# tmc4671_InterfaceConnectors.net
KiCad netlist of a schematic drawn in Altium Designer
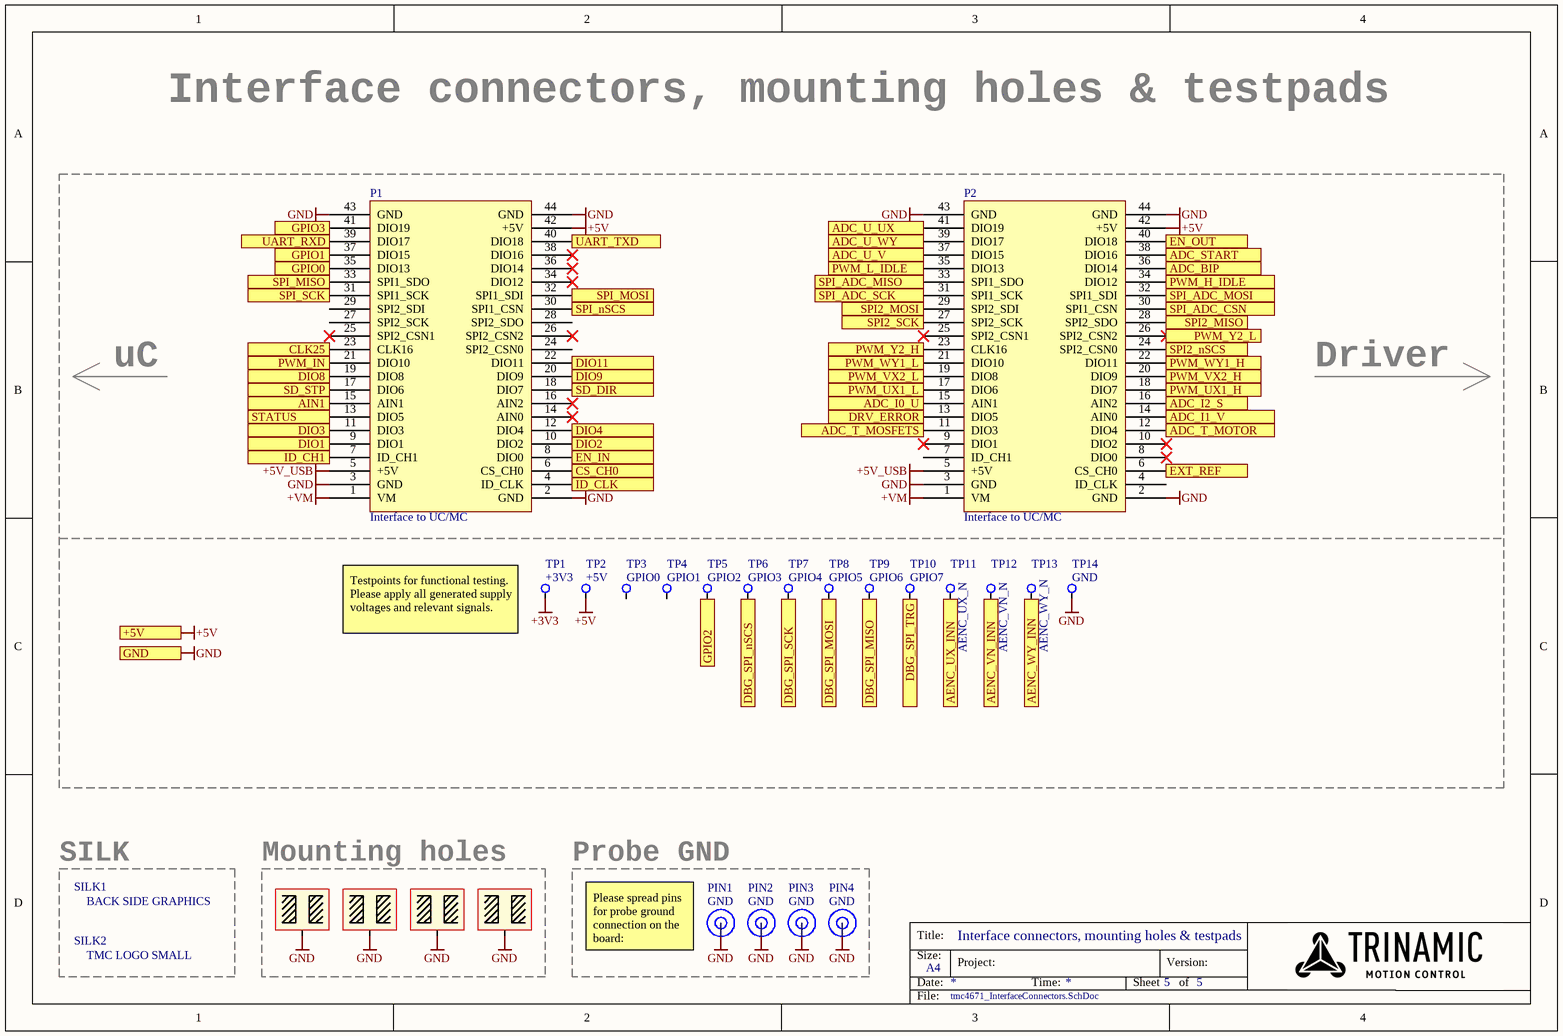
[diagram p0: tmc4671_InterfaceConnectors.SchDoc]

(export (version "E")
  (design (tool "Eeschema 10.0.6"))
  (components
    (comp (ref "MNT1")
      (value "MOUNTING_HOLE")
      (footprint "MNT_HOLE_6.35-3.2")
      (libsource (lib "TMC-EVAL_TMPL_V1_0") (part "MOUNTING_HOLE"))
    )
    (comp (ref "MNT2")
      (value "MOUNTING_HOLE")
      (footprint "MNT_HOLE_6.35-3.2")
      (libsource (lib "TMC-EVAL_TMPL_V1_0") (part "MOUNTING_HOLE"))
    )
    (comp (ref "MNT3")
      (value "MOUNTING_HOLE")
      (footprint "MNT_HOLE_6.35-3.2")
      (libsource (lib "TMC-EVAL_TMPL_V1_0") (part "MOUNTING_HOLE"))
    )
    (comp (ref "MNT4")
      (value "MOUNTING_HOLE")
      (footprint "MNT_HOLE_6.35-3.2")
      (libsource (lib "TMC-EVAL_TMPL_V1_0") (part "MOUNTING_HOLE"))
    )
    (comp (ref "P1")
      (value "Interface to UC/MC")
      (footprint "Interface_Connector")
      (description "Board-To-Board Connector, 2.54 mm, 44 Contacts, Receptacle, HLE Series, Surface Mount, 2 Rows")
      (fields (field (name "MF") "SAMTEC") (field (name "MPN") "HLE-122-02-L-DV"))
      (libsource (lib "TMC4671-EVAL_V1_0") (part "Interface Connector, 44 Pins"))
    )
    (comp (ref "P2")
      (value "Interface to UC/MC")
      (footprint "Interface_Connector")
      (description "Board-To-Board Connector, 2.54 mm, 44 Contacts, Receptacle, HLE Series, Surface Mount, 2 Rows")
      (fields (field (name "MF") "SAMTEC") (field (name "MPN") "HLE-122-02-L-DV"))
      (libsource (lib "TMC4671-EVAL_V1_0") (part "Interface Connector, 44 Pins"))
    )
    (comp (ref "PIN1")
      (value "GND")
      (footprint "TP_1.1-1.85_OCT")
      (description "TH testpoint, 1.1 hole, 1.85 pad, octagonal")
      (libsource (lib "TMC-EVAL_TMPL_V1_0") (part "TP_1.1-1.85_OCT"))
    )
    (comp (ref "PIN2")
      (value "GND")
      (footprint "TP_1.1-1.85_OCT")
      (description "TH testpoint, 1.1 hole, 1.85 pad, octagonal")
      (libsource (lib "TMC-EVAL_TMPL_V1_0") (part "TP_1.1-1.85_OCT"))
    )
    (comp (ref "PIN3")
      (value "GND")
      (footprint "TP_1.1-1.85_OCT")
      (description "TH testpoint, 1.1 hole, 1.85 pad, octagonal")
      (libsource (lib "TMC-EVAL_TMPL_V1_0") (part "TP_1.1-1.85_OCT"))
    )
    (comp (ref "PIN4")
      (value "GND")
      (footprint "TP_1.1-1.85_OCT")
      (description "TH testpoint, 1.1 hole, 1.85 pad, octagonal")
      (libsource (lib "TMC-EVAL_TMPL_V1_0") (part "TP_1.1-1.85_OCT"))
    )
    (comp (ref "SILK1")
      (value "BACK SIDE GRAPHICS")
      (footprint "TMC4671_EVAL_v1_0_back_label")
      (libsource (lib "TMC-EVAL_TMPL_V1_0") (part "SILK_GFX"))
    )
    (comp (ref "SILK2")
      (value "TMC LOGO SMALL")
      (footprint "TMC_logo_small")
      (libsource (lib "TMC-EVAL_TMPL_V1_0") (part "SILK_GFX"))
    )
    (comp (ref "TP1")
      (value "+3V3")
      (footprint "TP_SMD_1.2MM_ROUND")
      (description "SMD testpoint, 1.2mm pad, round")
      (libsource (lib "TMC-EVAL_TMPL_V1_0") (part "TP_SMD_Xmm"))
    )
    (comp (ref "TP2")
      (value "+5V")
      (footprint "TP_SMD_1.2MM_ROUND")
      (description "SMD testpoint, 1.2mm pad, round")
      (libsource (lib "TMC-EVAL_TMPL_V1_0") (part "TP_SMD_Xmm"))
    )
    (comp (ref "TP3")
      (value "GPIO0")
      (footprint "TP_SMD_1.2MM_ROUND")
      (description "SMD testpoint, 1.2mm pad, round")
      (libsource (lib "TMC-EVAL_TMPL_V1_0") (part "TP_SMD_Xmm"))
    )
    (comp (ref "TP4")
      (value "GPIO1")
      (footprint "TP_SMD_1.2MM_ROUND")
      (description "SMD testpoint, 1.2mm pad, round")
      (libsource (lib "TMC-EVAL_TMPL_V1_0") (part "TP_SMD_Xmm"))
    )
    (comp (ref "TP5")
      (value "GPIO2")
      (footprint "TP_SMD_1.2MM_ROUND")
      (description "SMD testpoint, 1.2mm pad, round")
      (libsource (lib "TMC-EVAL_TMPL_V1_0") (part "TP_SMD_Xmm"))
    )
    (comp (ref "TP6")
      (value "GPIO3")
      (footprint "TP_SMD_1.2MM_ROUND")
      (description "SMD testpoint, 1.2mm pad, round")
      (libsource (lib "TMC-EVAL_TMPL_V1_0") (part "TP_SMD_Xmm"))
    )
    (comp (ref "TP7")
      (value "GPIO4")
      (footprint "TP_SMD_1.2MM_ROUND")
      (description "SMD testpoint, 1.2mm pad, round")
      (libsource (lib "TMC-EVAL_TMPL_V1_0") (part "TP_SMD_Xmm"))
    )
    (comp (ref "TP8")
      (value "GPIO5")
      (footprint "TP_SMD_1.2MM_ROUND")
      (description "SMD testpoint, 1.2mm pad, round")
      (libsource (lib "TMC-EVAL_TMPL_V1_0") (part "TP_SMD_Xmm"))
    )
    (comp (ref "TP9")
      (value "GPIO6")
      (footprint "TP_SMD_1.2MM_ROUND")
      (description "SMD testpoint, 1.2mm pad, round")
      (libsource (lib "TMC-EVAL_TMPL_V1_0") (part "TP_SMD_Xmm"))
    )
    (comp (ref "TP10")
      (value "GPIO7")
      (footprint "TP_SMD_1.2MM_ROUND")
      (description "SMD testpoint, 1.2mm pad, round")
      (libsource (lib "TMC-EVAL_TMPL_V1_0") (part "TP_SMD_Xmm"))
    )
    (comp (ref "TP11")
      (value "AENC_UX_N")
      (footprint "TP_SMD_1.2MM_ROUND")
      (description "SMD testpoint, 1.2mm pad, round")
      (libsource (lib "TMC-EVAL_TMPL_V1_0") (part "TP_SMD_Xmm"))
    )
    (comp (ref "TP12")
      (value "AENC_VN_N")
      (footprint "TP_SMD_1.2MM_ROUND")
      (description "SMD testpoint, 1.2mm pad, round")
      (libsource (lib "TMC-EVAL_TMPL_V1_0") (part "TP_SMD_Xmm"))
    )
    (comp (ref "TP13")
      (value "AENC_WY_N")
      (footprint "TP_SMD_1.2MM_ROUND")
      (description "SMD testpoint, 1.2mm pad, round")
      (libsource (lib "TMC-EVAL_TMPL_V1_0") (part "TP_SMD_Xmm"))
    )
    (comp (ref "TP14")
      (value "GND")
      (footprint "TP_SMD_1.2MM_ROUND")
      (description "SMD testpoint, 1.2mm pad, round")
      (libsource (lib "TMC-EVAL_TMPL_V1_0") (part "TP_SMD_Xmm"))
    )
  )
  (nets
    (net (code "1") (name "+3V3") (class "Default")
      (node (ref "TP1") (pin "1") (pinfunction "1_1") (pintype "passive"))
    )
    (net (code "2") (name "+5V") (class "Default")
      (node (ref "P1") (pin "42") (pinfunction "+5V_42") (pintype "passive"))
      (node (ref "P2") (pin "42") (pinfunction "+5V_42") (pintype "passive"))
      (node (ref "TP2") (pin "1") (pinfunction "1_1") (pintype "passive"))
    )
    (net (code "3") (name "+5V_USB") (class "Default")
      (node (ref "P1") (pin "5") (pinfunction "+5V_5") (pintype "passive"))
      (node (ref "P2") (pin "5") (pinfunction "+5V_5") (pintype "passive"))
    )
    (net (code "4") (name "+VM") (class "Default")
      (node (ref "P1") (pin "1") (pinfunction "VM_1") (pintype "passive"))
      (node (ref "P2") (pin "1") (pinfunction "VM_1") (pintype "passive"))
    )
    (net (code "5") (name "/ADC_BIP") (class "Default")
      (node (ref "P2") (pin "36") (pinfunction "DIO14_36") (pintype "passive"))
    )
    (net (code "6") (name "/ADC_I0_U") (class "Default")
      (node (ref "P2") (pin "15") (pinfunction "AIN1_15") (pintype "passive"))
    )
    (net (code "7") (name "/ADC_I1_V") (class "Default")
      (node (ref "P2") (pin "14") (pinfunction "AIN0_14") (pintype "passive"))
    )
    (net (code "8") (name "/ADC_I2_S") (class "Default")
      (node (ref "P2") (pin "16") (pinfunction "AIN2_16") (pintype "passive"))
    )
    (net (code "9") (name "/ADC_START") (class "Default")
      (node (ref "P2") (pin "38") (pinfunction "DIO16_38") (pintype "passive"))
    )
    (net (code "10") (name "/ADC_T_MOSFETS") (class "Default")
      (node (ref "P2") (pin "11") (pinfunction "DIO3_11") (pintype "passive"))
    )
    (net (code "11") (name "/ADC_T_MOTOR") (class "Default")
      (node (ref "P2") (pin "12") (pinfunction "DIO4_12") (pintype "passive"))
    )
    (net (code "12") (name "/ADC_U_UX") (class "Default")
      (node (ref "P2") (pin "41") (pinfunction "DIO19_41") (pintype "passive"))
    )
    (net (code "13") (name "/ADC_U_V") (class "Default")
      (node (ref "P2") (pin "37") (pinfunction "DIO15_37") (pintype "passive"))
    )
    (net (code "14") (name "/ADC_U_WY") (class "Default")
      (node (ref "P2") (pin "39") (pinfunction "DIO17_39") (pintype "passive"))
    )
    (net (code "15") (name "/AENC_UX_INN") (class "Default")
      (node (ref "TP11") (pin "1") (pinfunction "1_1") (pintype "passive"))
    )
    (net (code "16") (name "/AENC_VN_INN") (class "Default")
      (node (ref "TP12") (pin "1") (pinfunction "1_1") (pintype "passive"))
    )
    (net (code "17") (name "/AENC_WY_INN") (class "Default")
      (node (ref "TP13") (pin "1") (pinfunction "1_1") (pintype "passive"))
    )
    (net (code "18") (name "/AIN1") (class "Default")
      (node (ref "P1") (pin "15") (pinfunction "AIN1_15") (pintype "passive"))
    )
    (net (code "19") (name "/CLK25") (class "Default")
      (node (ref "P1") (pin "23") (pinfunction "CLK16_23") (pintype "passive"))
    )
    (net (code "20") (name "/CS_CH0") (class "Default")
      (node (ref "P1") (pin "6") (pinfunction "CS_CH0_6") (pintype "passive"))
    )
    (net (code "21") (name "/DBG_SPI_MISO") (class "Default")
      (node (ref "TP9") (pin "1") (pinfunction "1_1") (pintype "passive"))
    )
    (net (code "22") (name "/DBG_SPI_MOSI") (class "Default")
      (node (ref "TP8") (pin "1") (pinfunction "1_1") (pintype "passive"))
    )
    (net (code "23") (name "/DBG_SPI_SCK") (class "Default")
      (node (ref "TP7") (pin "1") (pinfunction "1_1") (pintype "passive"))
    )
    (net (code "24") (name "/DBG_SPI_TRG") (class "Default")
      (node (ref "TP10") (pin "1") (pinfunction "1_1") (pintype "passive"))
    )
    (net (code "25") (name "/DBG_SPI_nSCS") (class "Default")
      (node (ref "TP6") (pin "1") (pinfunction "1_1") (pintype "passive"))
    )
    (net (code "26") (name "/DIO1") (class "Default")
      (node (ref "P1") (pin "9") (pinfunction "DIO1_9") (pintype "passive"))
    )
    (net (code "27") (name "/DIO2") (class "Default")
      (node (ref "P1") (pin "10") (pinfunction "DIO2_10") (pintype "passive"))
    )
    (net (code "28") (name "/DIO3") (class "Default")
      (node (ref "P1") (pin "11") (pinfunction "DIO3_11") (pintype "passive"))
    )
    (net (code "29") (name "/DIO4") (class "Default")
      (node (ref "P1") (pin "12") (pinfunction "DIO4_12") (pintype "passive"))
    )
    (net (code "30") (name "/DIO8") (class "Default")
      (node (ref "P1") (pin "19") (pinfunction "DIO8_19") (pintype "passive"))
    )
    (net (code "31") (name "/DIO9") (class "Default")
      (node (ref "P1") (pin "20") (pinfunction "DIO9_20") (pintype "passive"))
    )
    (net (code "32") (name "/DIO11") (class "Default")
      (node (ref "P1") (pin "22") (pinfunction "DIO11_22") (pintype "passive"))
    )
    (net (code "33") (name "/DRV_ERROR") (class "Default")
      (node (ref "P2") (pin "13") (pinfunction "DIO5_13") (pintype "passive"))
    )
    (net (code "34") (name "/EN_IN") (class "Default")
      (node (ref "P1") (pin "8") (pinfunction "DIO0_8") (pintype "passive"))
    )
    (net (code "35") (name "/EN_OUT") (class "Default")
      (node (ref "P2") (pin "40") (pinfunction "DIO18_40") (pintype "passive"))
    )
    (net (code "36") (name "/EXT_REF") (class "Default")
      (node (ref "P2") (pin "6") (pinfunction "CS_CH0_6") (pintype "passive"))
    )
    (net (code "37") (name "/GPIO0") (class "Default")
      (node (ref "P1") (pin "35") (pinfunction "DIO13_35") (pintype "passive"))
    )
    (net (code "38") (name "/GPIO1") (class "Default")
      (node (ref "P1") (pin "37") (pinfunction "DIO15_37") (pintype "passive"))
    )
    (net (code "39") (name "/GPIO2") (class "Default")
      (node (ref "TP5") (pin "1") (pinfunction "1_1") (pintype "passive"))
    )
    (net (code "40") (name "/GPIO3") (class "Default")
      (node (ref "P1") (pin "41") (pinfunction "DIO19_41") (pintype "passive"))
    )
    (net (code "41") (name "/ID_CH1") (class "Default")
      (node (ref "P1") (pin "7") (pinfunction "ID_CH1_7") (pintype "passive"))
    )
    (net (code "42") (name "/ID_CLK") (class "Default")
      (node (ref "P1") (pin "4") (pinfunction "ID_CLK_4") (pintype "passive"))
    )
    (net (code "43") (name "/PWM_H_IDLE") (class "Default")
      (node (ref "P2") (pin "34") (pinfunction "DIO12_34") (pintype "passive"))
    )
    (net (code "44") (name "/PWM_IN") (class "Default")
      (node (ref "P1") (pin "21") (pinfunction "DIO10_21") (pintype "passive"))
    )
    (net (code "45") (name "/PWM_L_IDLE") (class "Default")
      (node (ref "P2") (pin "35") (pinfunction "DIO13_35") (pintype "passive"))
    )
    (net (code "46") (name "/PWM_UX1_H") (class "Default")
      (node (ref "P2") (pin "18") (pinfunction "DIO7_18") (pintype "passive"))
    )
    (net (code "47") (name "/PWM_UX1_L") (class "Default")
      (node (ref "P2") (pin "17") (pinfunction "DIO6_17") (pintype "passive"))
    )
    (net (code "48") (name "/PWM_VX2_H") (class "Default")
      (node (ref "P2") (pin "20") (pinfunction "DIO9_20") (pintype "passive"))
    )
    (net (code "49") (name "/PWM_VX2_L") (class "Default")
      (node (ref "P2") (pin "19") (pinfunction "DIO8_19") (pintype "passive"))
    )
    (net (code "50") (name "/PWM_WY1_H") (class "Default")
      (node (ref "P2") (pin "22") (pinfunction "DIO11_22") (pintype "passive"))
    )
    (net (code "51") (name "/PWM_WY1_L") (class "Default")
      (node (ref "P2") (pin "21") (pinfunction "DIO10_21") (pintype "passive"))
    )
    (net (code "52") (name "/PWM_Y2_H") (class "Default")
      (node (ref "P2") (pin "23") (pinfunction "CLK16_23") (pintype "passive"))
    )
    (net (code "53") (name "/PWM_Y2_L") (class "Default")
      (node (ref "P2") (pin "26") (pinfunction "SPI2_CSN2_26") (pintype "passive+no_connect"))
    )
    (net (code "54") (name "/SD_DIR") (class "Default")
      (node (ref "P1") (pin "18") (pinfunction "DIO7_18") (pintype "passive"))
    )
    (net (code "55") (name "/SD_STP") (class "Default")
      (node (ref "P1") (pin "17") (pinfunction "DIO6_17") (pintype "passive"))
    )
    (net (code "56") (name "/SPI2_MISO") (class "Default")
      (node (ref "P2") (pin "28") (pinfunction "SPI2_SDO_28") (pintype "passive"))
    )
    (net (code "57") (name "/SPI2_MOSI") (class "Default")
      (node (ref "P2") (pin "29") (pinfunction "SPI2_SDI_29") (pintype "passive"))
    )
    (net (code "58") (name "/SPI2_SCK") (class "Default")
      (node (ref "P2") (pin "27") (pinfunction "SPI2_SCK_27") (pintype "passive"))
    )
    (net (code "59") (name "/SPI2_nSCS") (class "Default")
      (node (ref "P2") (pin "24") (pinfunction "SPI2_CSN0_24") (pintype "passive"))
    )
    (net (code "60") (name "/SPI_ADC_CSN") (class "Default")
      (node (ref "P2") (pin "30") (pinfunction "SPI1_CSN_30") (pintype "passive"))
    )
    (net (code "61") (name "/SPI_ADC_MISO") (class "Default")
      (node (ref "P2") (pin "33") (pinfunction "SPI1_SDO_33") (pintype "passive"))
    )
    (net (code "62") (name "/SPI_ADC_MOSI") (class "Default")
      (node (ref "P2") (pin "32") (pinfunction "SPI1_SDI_32") (pintype "passive"))
    )
    (net (code "63") (name "/SPI_ADC_SCK") (class "Default")
      (node (ref "P2") (pin "31") (pinfunction "SPI1_SCK_31") (pintype "passive"))
    )
    (net (code "64") (name "/SPI_MISO") (class "Default")
      (node (ref "P1") (pin "33") (pinfunction "SPI1_SDO_33") (pintype "passive"))
    )
    (net (code "65") (name "/SPI_MOSI") (class "Default")
      (node (ref "P1") (pin "32") (pinfunction "SPI1_SDI_32") (pintype "passive"))
    )
    (net (code "66") (name "/SPI_SCK") (class "Default")
      (node (ref "P1") (pin "31") (pinfunction "SPI1_SCK_31") (pintype "passive"))
    )
    (net (code "67") (name "/SPI_nSCS") (class "Default")
      (node (ref "P1") (pin "30") (pinfunction "SPI1_CSN_30") (pintype "passive"))
    )
    (net (code "68") (name "/STATUS") (class "Default")
      (node (ref "P1") (pin "13") (pinfunction "DIO5_13") (pintype "passive"))
    )
    (net (code "69") (name "/UART_RXD") (class "Default")
      (node (ref "P1") (pin "39") (pinfunction "DIO17_39") (pintype "passive"))
    )
    (net (code "70") (name "/UART_TXD") (class "Default")
      (node (ref "P1") (pin "40") (pinfunction "DIO18_40") (pintype "passive"))
    )
    (net (code "71") (name "GND") (class "Default")
      (node (ref "MNT1") (pin "1") (pinfunction "1_1") (pintype "passive"))
      (node (ref "MNT2") (pin "1") (pinfunction "1_1") (pintype "passive"))
      (node (ref "MNT3") (pin "1") (pinfunction "1_1") (pintype "passive"))
      (node (ref "MNT4") (pin "1") (pinfunction "1_1") (pintype "passive"))
      (node (ref "P1") (pin "2") (pinfunction "GND_2") (pintype "passive"))
      (node (ref "P1") (pin "3") (pinfunction "GND_3") (pintype "passive"))
      (node (ref "P1") (pin "43") (pinfunction "GND_43") (pintype "passive"))
      (node (ref "P1") (pin "44") (pinfunction "GND_44") (pintype "passive"))
      (node (ref "P2") (pin "2") (pinfunction "GND_2") (pintype "passive"))
      (node (ref "P2") (pin "3") (pinfunction "GND_3") (pintype "passive"))
      (node (ref "P2") (pin "43") (pinfunction "GND_43") (pintype "passive"))
      (node (ref "P2") (pin "44") (pinfunction "GND_44") (pintype "passive"))
      (node (ref "PIN1") (pin "1") (pinfunction "1_1") (pintype "power_in"))
      (node (ref "PIN2") (pin "1") (pinfunction "1_1") (pintype "power_in"))
      (node (ref "PIN3") (pin "1") (pinfunction "1_1") (pintype "power_in"))
      (node (ref "PIN4") (pin "1") (pinfunction "1_1") (pintype "power_in"))
      (node (ref "TP14") (pin "1") (pinfunction "1_1") (pintype "passive"))
    )
    (net (code "72") (name "unconnected-(P1-AIN0-Pad14)") (class "Default")
      (node (ref "P1") (pin "14") (pinfunction "AIN0_14") (pintype "passive+no_connect"))
    )
    (net (code "73") (name "unconnected-(P1-AIN2-Pad16)") (class "Default")
      (node (ref "P1") (pin "16") (pinfunction "AIN2_16") (pintype "passive+no_connect"))
    )
    (net (code "74") (name "unconnected-(P1-DIO12-Pad34)") (class "Default")
      (node (ref "P1") (pin "34") (pinfunction "DIO12_34") (pintype "passive+no_connect"))
    )
    (net (code "75") (name "unconnected-(P1-DIO14-Pad36)") (class "Default")
      (node (ref "P1") (pin "36") (pinfunction "DIO14_36") (pintype "passive+no_connect"))
    )
    (net (code "76") (name "unconnected-(P1-DIO16-Pad38)") (class "Default")
      (node (ref "P1") (pin "38") (pinfunction "DIO16_38") (pintype "passive+no_connect"))
    )
    (net (code "77") (name "unconnected-(P1-SPI2_CSN0-Pad24)") (class "Default")
      (node (ref "P1") (pin "24") (pinfunction "SPI2_CSN0_24") (pintype "passive"))
    )
    (net (code "78") (name "unconnected-(P1-SPI2_CSN1-Pad25)") (class "Default")
      (node (ref "P1") (pin "25") (pinfunction "SPI2_CSN1_25") (pintype "passive+no_connect"))
    )
    (net (code "79") (name "unconnected-(P1-SPI2_CSN2-Pad26)") (class "Default")
      (node (ref "P1") (pin "26") (pinfunction "SPI2_CSN2_26") (pintype "passive+no_connect"))
    )
    (net (code "80") (name "unconnected-(P1-SPI2_SCK-Pad27)") (class "Default")
      (node (ref "P1") (pin "27") (pinfunction "SPI2_SCK_27") (pintype "passive"))
    )
    (net (code "81") (name "unconnected-(P1-SPI2_SDI-Pad29)") (class "Default")
      (node (ref "P1") (pin "29") (pinfunction "SPI2_SDI_29") (pintype "passive"))
    )
    (net (code "82") (name "unconnected-(P1-SPI2_SDO-Pad28)") (class "Default")
      (node (ref "P1") (pin "28") (pinfunction "SPI2_SDO_28") (pintype "passive"))
    )
    (net (code "83") (name "unconnected-(P2-DIO0-Pad8)") (class "Default")
      (node (ref "P2") (pin "8") (pinfunction "DIO0_8") (pintype "passive+no_connect"))
    )
    (net (code "84") (name "unconnected-(P2-DIO1-Pad9)") (class "Default")
      (node (ref "P2") (pin "9") (pinfunction "DIO1_9") (pintype "passive+no_connect"))
    )
    (net (code "85") (name "unconnected-(P2-DIO2-Pad10)") (class "Default")
      (node (ref "P2") (pin "10") (pinfunction "DIO2_10") (pintype "passive+no_connect"))
    )
    (net (code "86") (name "unconnected-(P2-ID_CH1-Pad7)") (class "Default")
      (node (ref "P2") (pin "7") (pinfunction "ID_CH1_7") (pintype "passive"))
    )
    (net (code "87") (name "unconnected-(P2-ID_CLK-Pad4)") (class "Default")
      (node (ref "P2") (pin "4") (pinfunction "ID_CLK_4") (pintype "passive"))
    )
    (net (code "88") (name "unconnected-(P2-SPI2_CSN1-Pad25)") (class "Default")
      (node (ref "P2") (pin "25") (pinfunction "SPI2_CSN1_25") (pintype "passive+no_connect"))
    )
    (net (code "89") (name "unconnected-(TP3-Pad1)") (class "Default")
      (node (ref "TP3") (pin "1") (pinfunction "1_1") (pintype "passive"))
    )
    (net (code "90") (name "unconnected-(TP4-Pad1)") (class "Default")
      (node (ref "TP4") (pin "1") (pinfunction "1_1") (pintype "passive"))
    )
  )
)
